# waterius-homemade_heat_counter.net
KiCad netlist of a schematic drawn in EAGLE
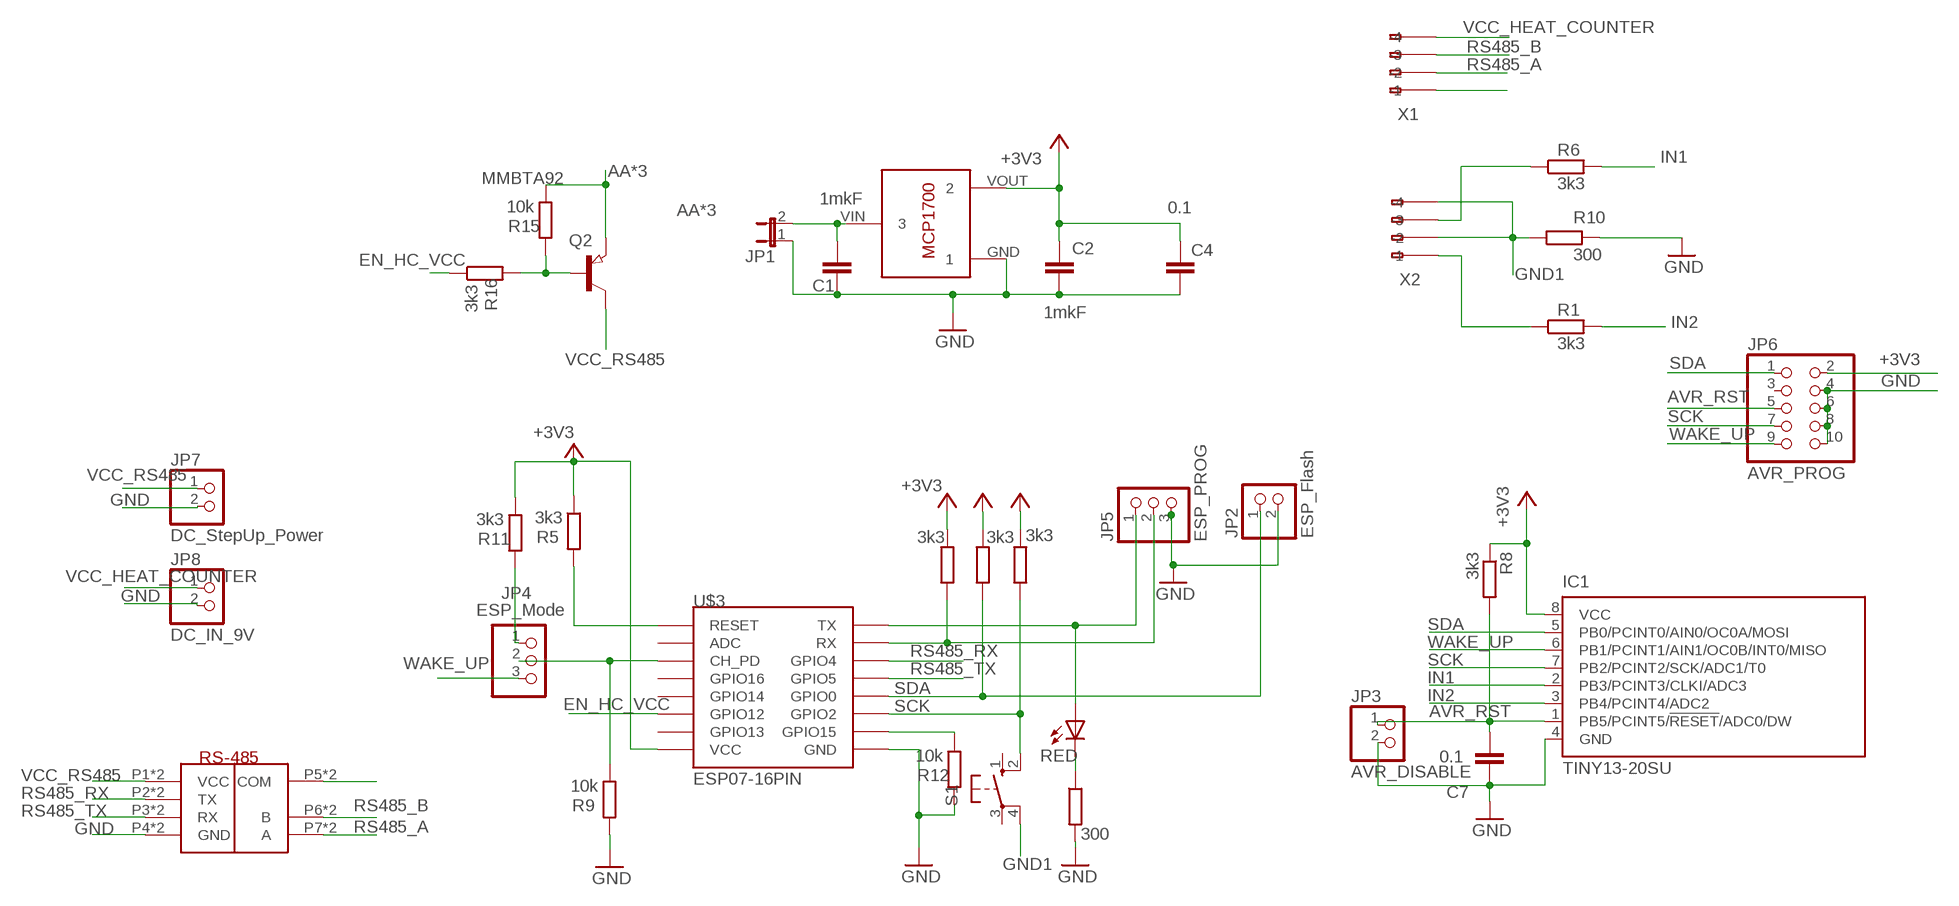
[diagram p0: schematic, sheet 1]

(export (version "E")
  (design (tool "Eeschema 10.0.6"))
  (components
    (comp (ref "C1")
      (value "1mkF")
      (footprint "eagle-import:C0805")
      (libsource (lib "eagle-import") (part "resistor_348_C-EUC0805"))
    )
    (comp (ref "C2")
      (value "1mkF")
      (footprint "eagle-import:C0805")
      (libsource (lib "eagle-import") (part "resistor_348_C-EUC0805"))
    )
    (comp (ref "C4")
      (value "0.1")
      (footprint "eagle-import:C0805")
      (libsource (lib "eagle-import") (part "C-EUC0805"))
    )
    (comp (ref "C7")
      (value "0.1")
      (footprint "eagle-import:C0805")
      (libsource (lib "eagle-import") (part "resistor_348_C-EUC0805"))
    )
    (comp (ref "IC1")
      (value "TINY13-20SU")
      (footprint "eagle-import:8S2")
      (fields (field (name "MPN") "ATTINY13-20SU"))
      (libsource (lib "eagle-import") (part "TINY13SU-20"))
    )
    (comp (ref "JP1")
      (value "JP1E")
      (footprint "eagle-import:JP1")
      (libsource (lib "eagle-import") (part "JP1E"))
    )
    (comp (ref "JP2")
      (value "ESP_Flash")
      (footprint "eagle-import:1X02")
      (libsource (lib "eagle-import") (part "PINHD-1X2"))
    )
    (comp (ref "JP3")
      (value "AVR_DISABLE")
      (footprint "eagle-import:1X02")
      (libsource (lib "eagle-import") (part "PINHD-1X2"))
    )
    (comp (ref "JP4")
      (value "ESP_Mode")
      (footprint "eagle-import:1X03")
      (libsource (lib "eagle-import") (part "PINHD-1X3"))
    )
    (comp (ref "JP5")
      (value "ESP_PROG")
      (footprint "eagle-import:1X03")
      (libsource (lib "eagle-import") (part "PINHD-1X3"))
    )
    (comp (ref "JP6")
      (value "AVR_PROG")
      (footprint "eagle-import:2X05")
      (libsource (lib "eagle-import") (part "PINHD-2X5"))
    )
    (comp (ref "JP7")
      (value "DC_StepUp_Power")
      (footprint "eagle-import:1X02")
      (libsource (lib "eagle-import") (part "PINHD-1X2"))
    )
    (comp (ref "JP8")
      (value "DC_IN_9V")
      (footprint "eagle-import:1X02")
      (libsource (lib "eagle-import") (part "PINHD-1X2"))
    )
    (comp (ref "LED1")
      (value "RED")
      (footprint "eagle-import:CHIPLED_0805")
      (libsource (lib "eagle-import") (part "LEDCHIPLED_0805"))
    )
    (comp (ref "Q2")
      (value "MMBTA92")
      (footprint "eagle-import:SOT23")
      (libsource (lib "eagle-import") (part "PNP-TRANSISTOR_SOT23"))
    )
    (comp (ref "R1")
      (value "3k3")
      (footprint "eagle-import:M0805")
      (fields (field (name "SPICEPREFIX") "R"))
      (libsource (lib "eagle-import") (part "resistor_348_R-EU_M0805"))
    )
    (comp (ref "R2")
      (value "3k3")
      (footprint "eagle-import:R0805")
      (fields (field (name "OM") "3k6"))
      (libsource (lib "eagle-import") (part "R-EU_R0805"))
    )
    (comp (ref "R3")
      (value "3k3")
      (footprint "eagle-import:R0805")
      (fields (field (name "OM") "3k6"))
      (libsource (lib "eagle-import") (part "rcl_334_R-EU_R0805"))
    )
    (comp (ref "R4")
      (value "300")
      (footprint "eagle-import:R0805")
      (fields (field (name "OM") "200"))
      (libsource (lib "eagle-import") (part "rcl_334_R-EU_R0805"))
    )
    (comp (ref "R5")
      (value "3k3")
      (footprint "eagle-import:R0805")
      (fields (field (name "OM") "3k6"))
      (libsource (lib "eagle-import") (part "R-EU_R0805"))
    )
    (comp (ref "R6")
      (value "3k3")
      (footprint "eagle-import:M0805")
      (libsource (lib "eagle-import") (part "resistor_348_R-EU_M0805"))
    )
    (comp (ref "R7")
      (value "3k3")
      (footprint "eagle-import:R0805")
      (fields (field (name "OM") "3k6"))
      (libsource (lib "eagle-import") (part "R-EU_R0805"))
    )
    (comp (ref "R8")
      (value "3k3")
      (footprint "eagle-import:R0805")
      (fields (field (name "OM") "3k6"))
      (libsource (lib "eagle-import") (part "rcl_334_R-EU_R0805"))
    )
    (comp (ref "R9")
      (value "10k")
      (footprint "eagle-import:R0805")
      (fields (field (name "OM") "3k6"))
      (libsource (lib "eagle-import") (part "R-EU_R0805"))
    )
    (comp (ref "R10")
      (value "300")
      (footprint "eagle-import:M0805")
      (libsource (lib "eagle-import") (part "resistor_348_R-EU_M0805"))
    )
    (comp (ref "R11")
      (value "3k3")
      (footprint "eagle-import:R0805")
      (fields (field (name "OM") "3k6"))
      (libsource (lib "eagle-import") (part "R-EU_R0805"))
    )
    (comp (ref "R12")
      (value "10k")
      (footprint "eagle-import:R0805")
      (fields (field (name "OM") "3k6"))
      (libsource (lib "eagle-import") (part "R-EU_R0805"))
    )
    (comp (ref "R15")
      (value "10k")
      (footprint "eagle-import:R0805")
      (fields (field (name "OM") "3k6"))
      (libsource (lib "eagle-import") (part "R-EU_R0805"))
    )
    (comp (ref "R16")
      (value "3k3")
      (footprint "eagle-import:R0805")
      (fields (field (name "OM") "3k6"))
      (libsource (lib "eagle-import") (part "R-EU_R0805"))
    )
    (comp (ref "S1")
      (value "10-XX")
      (footprint "eagle-import:B3F-10XX")
      (fields (field (name "MPN") "B3F-1000"))
      (libsource (lib "eagle-import") (part "10-XX"))
    )
    (comp (ref "U$2")
      (value "MCP1700T-3302E/TT")
      (footprint "eagle-import:MCP1700T-3302E_TT")
      (libsource (lib "eagle-import") (part "MCP1700T-3302E/TT"))
    )
    (comp (ref "U$3")
      (value "ESP07-16PIN")
      (footprint "eagle-import:ESP07-16PIN")
      (libsource (lib "eagle-import") (part "ESP07-16PIN"))
    )
    (comp (ref "U1")
      (value "RS-485-MODULE")
      (footprint "eagle-import:DIP_MODULE")
      (libsource (lib "eagle-import") (part "RS-485-MODULE"))
    )
    (comp (ref "X1")
      (value "233-104")
      (footprint "eagle-import:233-104")
      (libsource (lib "eagle-import") (part "233-104"))
    )
    (comp (ref "X2")
      (value "233-104")
      (footprint "eagle-import:233-104")
      (libsource (lib "eagle-import") (part "233-104"))
    )
  )
  (nets
    (net (code "1") (name "+3V3") (class "Default")
      (node (ref "C2") (pin "1") (pinfunction "1_1") (pintype "passive"))
      (node (ref "C4") (pin "1") (pinfunction "1_1") (pintype "passive"))
      (node (ref "IC1") (pin "8") (pinfunction "VCC_8") (pintype "power_in"))
      (node (ref "JP6") (pin "2") (pinfunction "2_2") (pintype "passive"))
      (node (ref "R11") (pin "1") (pinfunction "1_1") (pintype "passive"))
      (node (ref "R2") (pin "1") (pinfunction "1_1") (pintype "passive"))
      (node (ref "R3") (pin "1") (pinfunction "1_1") (pintype "passive"))
      (node (ref "R5") (pin "1") (pinfunction "1_1") (pintype "passive"))
      (node (ref "R7") (pin "1") (pinfunction "1_1") (pintype "passive"))
      (node (ref "R8") (pin "1") (pinfunction "1_1") (pintype "passive"))
      (node (ref "U$2") (pin "VOUT") (pinfunction "2_VOUT") (pintype "bidirectional"))
      (node (ref "U$3") (pin "VCC") (pinfunction "VCC_VCC") (pintype "bidirectional"))
    )
    (net (code "2") (name "/AA*3") (class "Default")
      (node (ref "C1") (pin "1") (pinfunction "1_1") (pintype "passive"))
      (node (ref "JP1") (pin "2") (pinfunction "2_2") (pintype "passive"))
      (node (ref "Q2") (pin "2") (pinfunction "E_2") (pintype "passive"))
      (node (ref "R15") (pin "1") (pinfunction "1_1") (pintype "passive"))
      (node (ref "U$2") (pin "VIN") (pinfunction "3_VIN") (pintype "bidirectional"))
    )
    (net (code "3") (name "/AVR_RST") (class "Default")
      (node (ref "C7") (pin "2") (pinfunction "2_2") (pintype "passive"))
      (node (ref "IC1") (pin "1") (pinfunction "PB5/PCINT5/~{RESET}/ADC0/DW_1") (pintype "bidirectional"))
      (node (ref "JP3") (pin "1") (pinfunction "1_1") (pintype "passive"))
      (node (ref "JP6") (pin "5") (pinfunction "5_5") (pintype "passive"))
      (node (ref "R8") (pin "2") (pinfunction "2_2") (pintype "passive"))
    )
    (net (code "4") (name "/EN_HC_VCC") (class "Default")
      (node (ref "R16") (pin "1") (pinfunction "1_1") (pintype "passive"))
      (node (ref "U$3") (pin "GPIO12") (pinfunction "GPIO12_GPIO12") (pintype "bidirectional"))
    )
    (net (code "5") (name "/GND1") (class "Default")
      (node (ref "R10") (pin "1") (pinfunction "1_1") (pintype "passive"))
      (node (ref "S1") (pin "4") (pinfunction "P1_4") (pintype "passive"))
      (node (ref "X2") (pin "A2") (pinfunction "-2_A2") (pintype "passive"))
      (node (ref "X2") (pin "A4") (pinfunction "-4_A4") (pintype "passive"))
    )
    (net (code "6") (name "/IN1") (class "Default")
      (node (ref "IC1") (pin "2") (pinfunction "PB3/PCINT3/CLKI/ADC3_2") (pintype "bidirectional"))
      (node (ref "R6") (pin "2") (pinfunction "2_2") (pintype "passive"))
    )
    (net (code "7") (name "/IN2") (class "Default")
      (node (ref "IC1") (pin "3") (pinfunction "PB4/PCINT4/ADC2_3") (pintype "bidirectional"))
      (node (ref "R1") (pin "2") (pinfunction "2_2") (pintype "passive"))
    )
    (net (code "8") (name "/RS485_A") (class "Default")
      (node (ref "U1") (pin "P7") (pinfunction "A_P7") (pintype "bidirectional"))
      (node (ref "U1") (pin "P8") (pinfunction "A_P8") (pintype "bidirectional"))
      (node (ref "X1") (pin "A2") (pinfunction "-2_A2") (pintype "passive"))
    )
    (net (code "9") (name "/RS485_B") (class "Default")
      (node (ref "U1") (pin "P6") (pinfunction "B_P6") (pintype "bidirectional"))
      (node (ref "U1") (pin "P9") (pinfunction "B_P9") (pintype "bidirectional"))
      (node (ref "X1") (pin "A3") (pinfunction "-3_A3") (pintype "passive"))
    )
    (net (code "10") (name "/RS485_RX") (class "Default")
      (node (ref "U$3") (pin "GPIO4") (pinfunction "GPIO4_GPIO4") (pintype "bidirectional"))
      (node (ref "U1") (pin "P11") (pinfunction "TX_P11") (pintype "bidirectional"))
      (node (ref "U1") (pin "P2") (pinfunction "TX_P2") (pintype "bidirectional"))
    )
    (net (code "11") (name "/RS485_TX") (class "Default")
      (node (ref "U$3") (pin "GPIO5") (pinfunction "GPIO5_GPIO5") (pintype "bidirectional"))
      (node (ref "U1") (pin "P12") (pinfunction "RX_P12") (pintype "bidirectional"))
      (node (ref "U1") (pin "P3") (pinfunction "RX_P3") (pintype "bidirectional"))
    )
    (net (code "12") (name "/SCK") (class "Default")
      (node (ref "IC1") (pin "7") (pinfunction "PB2/PCINT2/SCK/ADC1/T0_7") (pintype "bidirectional"))
      (node (ref "JP6") (pin "7") (pinfunction "7_7") (pintype "passive"))
      (node (ref "R2") (pin "2") (pinfunction "2_2") (pintype "passive"))
      (node (ref "S1") (pin "2") (pinfunction "S1_2") (pintype "passive"))
      (node (ref "U$3") (pin "GPIO2") (pinfunction "GPIO2_GPIO2") (pintype "bidirectional"))
    )
    (net (code "13") (name "/SDA") (class "Default")
      (node (ref "IC1") (pin "5") (pinfunction "PB0/PCINT0/AIN0/OC0A/MOSI_5") (pintype "bidirectional"))
      (node (ref "JP2") (pin "1") (pinfunction "1_1") (pintype "passive"))
      (node (ref "JP6") (pin "1") (pinfunction "1_1") (pintype "passive"))
      (node (ref "R3") (pin "2") (pinfunction "2_2") (pintype "passive"))
      (node (ref "U$3") (pin "GPIO0") (pinfunction "GPIO0_GPIO0") (pintype "bidirectional"))
    )
    (net (code "14") (name "/VCC_HEAT_COUNTER") (class "Default")
      (node (ref "JP8") (pin "1") (pinfunction "1_1") (pintype "passive"))
      (node (ref "X1") (pin "A4") (pinfunction "-4_A4") (pintype "passive"))
    )
    (net (code "15") (name "/VCC_RS485") (class "Default")
      (node (ref "JP7") (pin "1") (pinfunction "1_1") (pintype "passive"))
      (node (ref "Q2") (pin "3") (pinfunction "C_3") (pintype "passive"))
      (node (ref "U1") (pin "P1") (pinfunction "VCC_P1") (pintype "power_in"))
      (node (ref "U1") (pin "P10") (pinfunction "VCC_P10") (pintype "power_in"))
    )
    (net (code "16") (name "/WAKE_UP") (class "Default")
      (node (ref "IC1") (pin "6") (pinfunction "PB1/PCINT1/AIN1/OC0B/INT0/MISO_6") (pintype "bidirectional"))
      (node (ref "JP4") (pin "3") (pinfunction "3_3") (pintype "passive"))
      (node (ref "JP6") (pin "9") (pinfunction "9_9") (pintype "passive"))
    )
    (net (code "17") (name "GND") (class "Default")
      (node (ref "C1") (pin "2") (pinfunction "2_2") (pintype "passive"))
      (node (ref "C2") (pin "2") (pinfunction "2_2") (pintype "passive"))
      (node (ref "C4") (pin "2") (pinfunction "2_2") (pintype "passive"))
      (node (ref "C7") (pin "1") (pinfunction "1_1") (pintype "passive"))
      (node (ref "IC1") (pin "4") (pinfunction "GND_4") (pintype "power_in"))
      (node (ref "JP1") (pin "1") (pinfunction "1_1") (pintype "passive"))
      (node (ref "JP2") (pin "2") (pinfunction "2_2") (pintype "passive"))
      (node (ref "JP3") (pin "2") (pinfunction "2_2") (pintype "passive"))
      (node (ref "JP5") (pin "3") (pinfunction "3_3") (pintype "passive"))
      (node (ref "JP6") (pin "10") (pinfunction "10_10") (pintype "passive"))
      (node (ref "JP6") (pin "4") (pinfunction "4_4") (pintype "passive"))
      (node (ref "JP6") (pin "6") (pinfunction "6_6") (pintype "passive"))
      (node (ref "JP6") (pin "8") (pinfunction "8_8") (pintype "passive"))
      (node (ref "JP7") (pin "2") (pinfunction "2_2") (pintype "passive"))
      (node (ref "JP8") (pin "2") (pinfunction "2_2") (pintype "passive"))
      (node (ref "R10") (pin "2") (pinfunction "2_2") (pintype "passive"))
      (node (ref "R12") (pin "2") (pinfunction "2_2") (pintype "passive"))
      (node (ref "R4") (pin "2") (pinfunction "2_2") (pintype "passive"))
      (node (ref "R9") (pin "2") (pinfunction "2_2") (pintype "passive"))
      (node (ref "U$2") (pin "GND") (pinfunction "1_GND") (pintype "bidirectional"))
      (node (ref "U$3") (pin "GND") (pinfunction "GND_GND") (pintype "bidirectional"))
      (node (ref "U1") (pin "P13") (pinfunction "GND_P13") (pintype "power_in"))
      (node (ref "U1") (pin "P4") (pinfunction "GND_P4") (pintype "power_in"))
    )
    (net (code "18") (name "Net-(JP4-Pad1)") (class "Default")
      (node (ref "JP4") (pin "1") (pinfunction "1_1") (pintype "passive"))
      (node (ref "R11") (pin "2") (pinfunction "2_2") (pintype "passive"))
    )
    (net (code "19") (name "Net-(JP4-Pad2)") (class "Default")
      (node (ref "JP4") (pin "2") (pinfunction "2_2") (pintype "passive"))
      (node (ref "R9") (pin "1") (pinfunction "1_1") (pintype "passive"))
      (node (ref "U$3") (pin "CH_PD") (pinfunction "CH_PD_CH_PD") (pintype "bidirectional"))
    )
    (net (code "20") (name "Net-(JP5-Pad1)") (class "Default")
      (node (ref "JP5") (pin "1") (pinfunction "1_1") (pintype "passive"))
      (node (ref "LED1") (pin "A") (pinfunction "A_A") (pintype "passive"))
      (node (ref "U$3") (pin "TX") (pinfunction "TX_TX") (pintype "bidirectional"))
    )
    (net (code "21") (name "Net-(JP5-Pad2)") (class "Default")
      (node (ref "JP5") (pin "2") (pinfunction "2_2") (pintype "passive"))
      (node (ref "R7") (pin "2") (pinfunction "2_2") (pintype "passive"))
      (node (ref "U$3") (pin "RX") (pinfunction "RX_RX") (pintype "bidirectional"))
    )
    (net (code "22") (name "Net-(LED1-PadC)") (class "Default")
      (node (ref "LED1") (pin "C") (pinfunction "C_C") (pintype "passive"))
      (node (ref "R4") (pin "1") (pinfunction "1_1") (pintype "passive"))
    )
    (net (code "23") (name "Net-(Q2-B)") (class "Default")
      (node (ref "Q2") (pin "1") (pinfunction "B_1") (pintype "passive"))
      (node (ref "R15") (pin "2") (pinfunction "2_2") (pintype "passive"))
      (node (ref "R16") (pin "2") (pinfunction "2_2") (pintype "passive"))
    )
    (net (code "24") (name "Net-(R12-Pad1)") (class "Default")
      (node (ref "R12") (pin "1") (pinfunction "1_1") (pintype "passive"))
      (node (ref "U$3") (pin "GPIO15") (pinfunction "GPIO15_GPIO15") (pintype "bidirectional"))
    )
    (net (code "25") (name "Net-(U$3-RESET)") (class "Default")
      (node (ref "R5") (pin "2") (pinfunction "2_2") (pintype "passive"))
      (node (ref "U$3") (pin "REST") (pinfunction "RESET_REST") (pintype "bidirectional"))
    )
    (net (code "26") (name "Net-(U1-COM-PadP14)") (class "Default")
      (node (ref "U1") (pin "P14") (pinfunction "COM_P14") (pintype "power_in"))
      (node (ref "U1") (pin "P5") (pinfunction "COM_P5") (pintype "power_in"))
    )
    (net (code "27") (name "Net-(X2--1)") (class "Default")
      (node (ref "R1") (pin "1") (pinfunction "1_1") (pintype "passive"))
      (node (ref "X2") (pin "A1") (pinfunction "-1_A1") (pintype "passive"))
    )
    (net (code "28") (name "Net-(X2--3)") (class "Default")
      (node (ref "R6") (pin "1") (pinfunction "1_1") (pintype "passive"))
      (node (ref "X2") (pin "A3") (pinfunction "-3_A3") (pintype "passive"))
    )
    (net (code "29") (name "unconnected-(JP6-Pad3)") (class "Default")
      (node (ref "JP6") (pin "3") (pinfunction "3_3") (pintype "passive"))
    )
    (net (code "30") (name "unconnected-(S1-P-Pad3)") (class "Default")
      (node (ref "S1") (pin "3") (pinfunction "P_3") (pintype "passive"))
    )
    (net (code "31") (name "unconnected-(S1-S-Pad1)") (class "Default")
      (node (ref "S1") (pin "1") (pinfunction "S_1") (pintype "passive"))
    )
    (net (code "32") (name "unconnected-(U$3-PadADC)") (class "Default")
      (node (ref "U$3") (pin "ADC") (pinfunction "ADC_ADC") (pintype "bidirectional"))
    )
    (net (code "33") (name "unconnected-(U$3-PadGPIO13)") (class "Default")
      (node (ref "U$3") (pin "GPIO13") (pinfunction "GPIO13_GPIO13") (pintype "bidirectional"))
    )
    (net (code "34") (name "unconnected-(U$3-PadGPIO14)") (class "Default")
      (node (ref "U$3") (pin "GPIO14") (pinfunction "GPIO14_GPIO14") (pintype "bidirectional"))
    )
    (net (code "35") (name "unconnected-(U$3-PadGPIO16)") (class "Default")
      (node (ref "U$3") (pin "GPIO16") (pinfunction "GPIO16_GPIO16") (pintype "bidirectional"))
    )
    (net (code "36") (name "unconnected-(X1--1-PadA1)") (class "Default")
      (node (ref "X1") (pin "A1") (pinfunction "-1_A1") (pintype "passive"))
    )
    (net (code "37") (name "unconnected-(X1-B-1-PadB1)") (class "Default")
      (node (ref "X1") (pin "B1") (pinfunction "B-1_B1") (pintype "passive"))
    )
    (net (code "38") (name "unconnected-(X1-B-2-PadB2)") (class "Default")
      (node (ref "X1") (pin "B2") (pinfunction "B-2_B2") (pintype "passive"))
    )
    (net (code "39") (name "unconnected-(X1-B-3-PadB3)") (class "Default")
      (node (ref "X1") (pin "B3") (pinfunction "B-3_B3") (pintype "passive"))
    )
    (net (code "40") (name "unconnected-(X1-B-4-PadB4)") (class "Default")
      (node (ref "X1") (pin "B4") (pinfunction "B-4_B4") (pintype "passive"))
    )
    (net (code "41") (name "unconnected-(X2-B-1-PadB1)") (class "Default")
      (node (ref "X2") (pin "B1") (pinfunction "B-1_B1") (pintype "passive"))
    )
    (net (code "42") (name "unconnected-(X2-B-2-PadB2)") (class "Default")
      (node (ref "X2") (pin "B2") (pinfunction "B-2_B2") (pintype "passive"))
    )
    (net (code "43") (name "unconnected-(X2-B-3-PadB3)") (class "Default")
      (node (ref "X2") (pin "B3") (pinfunction "B-3_B3") (pintype "passive"))
    )
    (net (code "44") (name "unconnected-(X2-B-4-PadB4)") (class "Default")
      (node (ref "X2") (pin "B4") (pinfunction "B-4_B4") (pintype "passive"))
    )
  )
)
